# Adafruit_SHT40.net
KiCad netlist of a schematic drawn in EAGLE
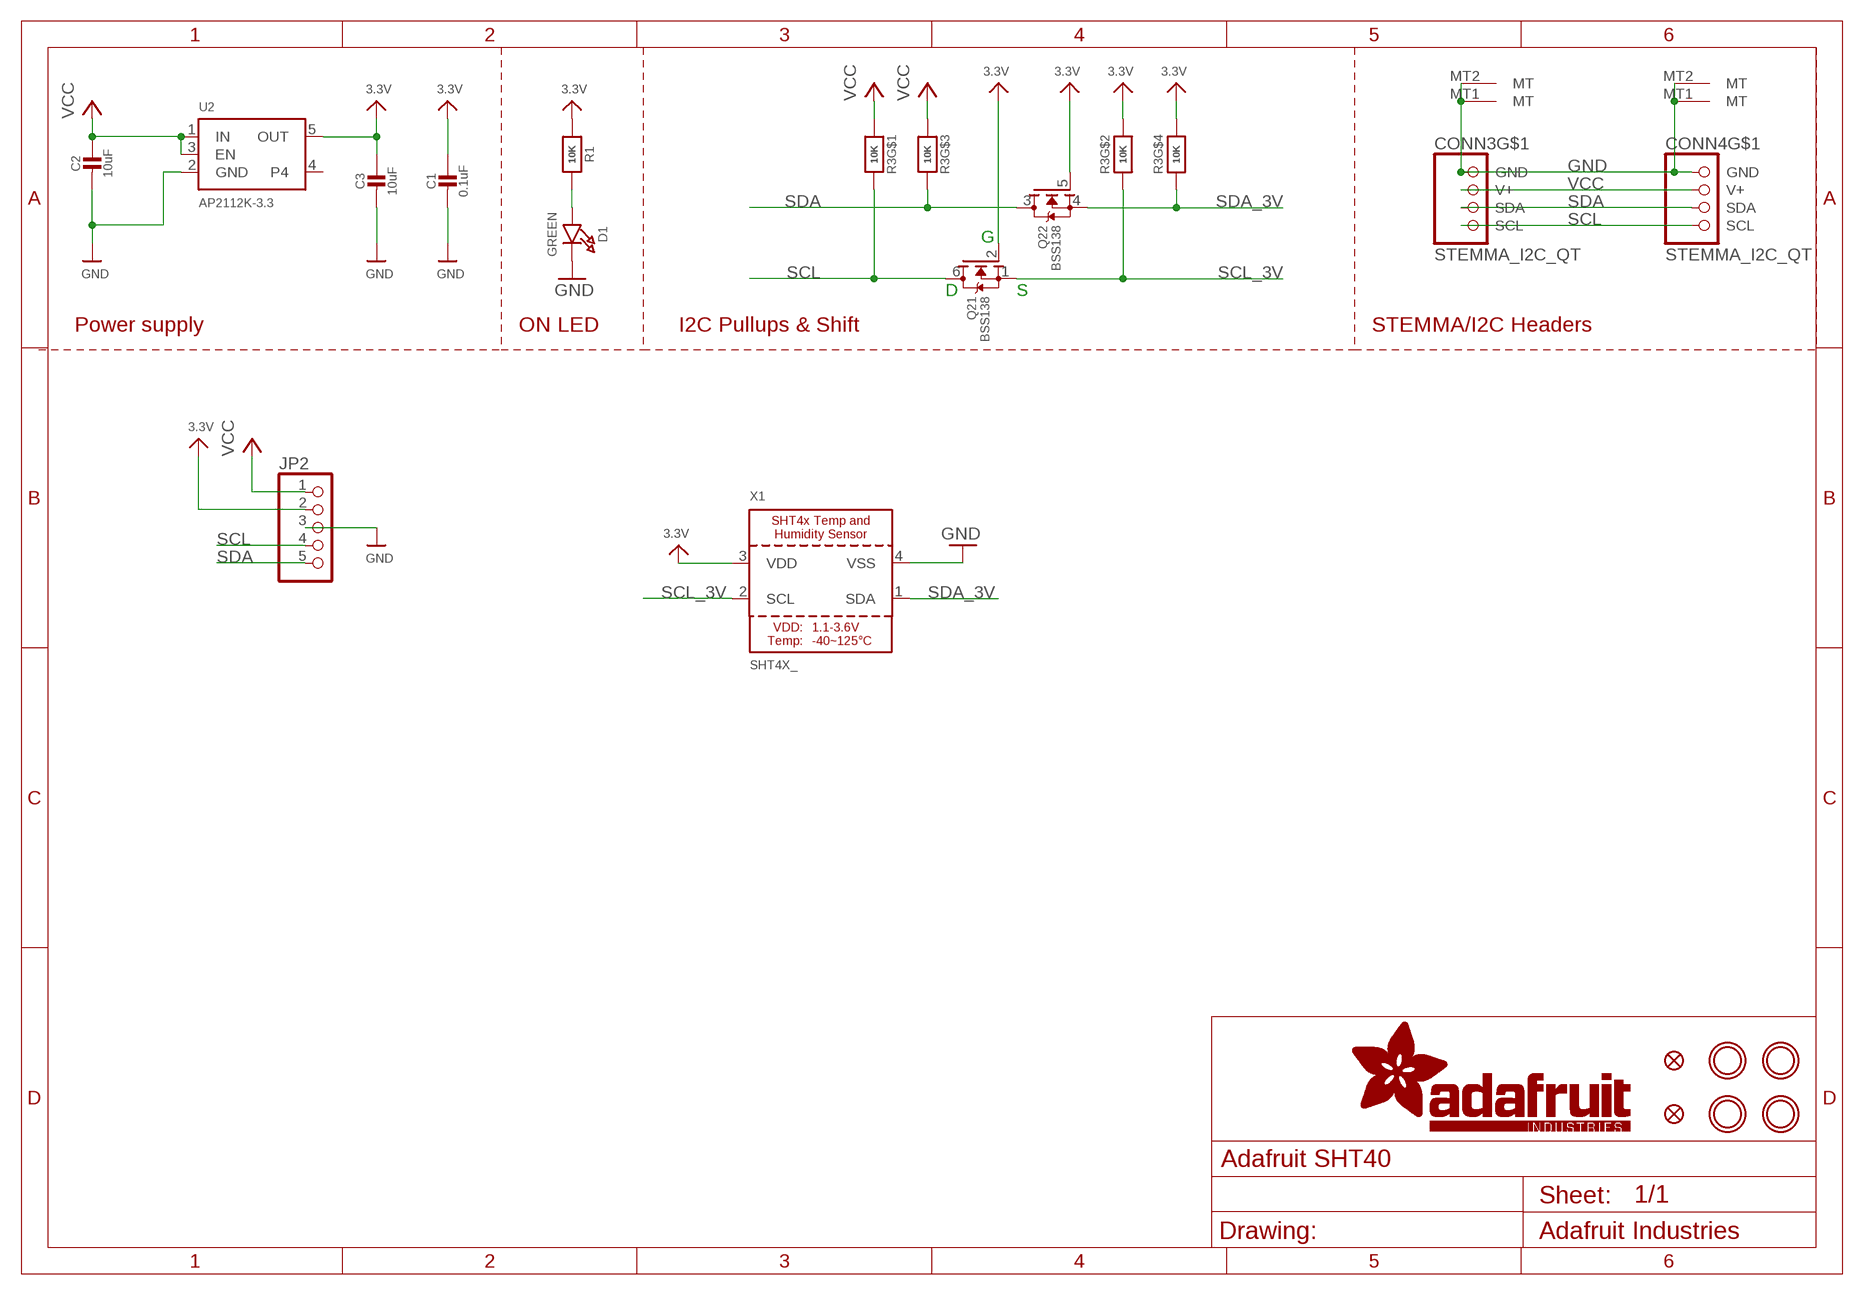
[diagram p0: schematic, sheet 1]

(export (version "E")
  (design (tool "Eeschema 10.0.6"))
  (components
    (comp (ref "C1")
      (value "0.1uF")
      (footprint "eagle-import:0603-NO")
      (libsource (lib "eagle-import") (part "CAP_CERAMIC0603_NO"))
    )
    (comp (ref "C2")
      (value "10uF")
      (footprint "eagle-import:0805-NO")
      (libsource (lib "eagle-import") (part "CAP_CERAMIC0805-NOOUTLINE"))
    )
    (comp (ref "C3")
      (value "10uF")
      (footprint "eagle-import:0805-NO")
      (libsource (lib "eagle-import") (part "CAP_CERAMIC0805-NOOUTLINE"))
    )
    (comp (ref "CONN3")
      (value "STEMMA_I2C_QT")
      (footprint "eagle-import:JST_SH4")
      (libsource (lib "eagle-import") (part "STEMMA_I2C_QT"))
    )
    (comp (ref "CONN4")
      (value "STEMMA_I2C_QT")
      (footprint "eagle-import:JST_SH4")
      (libsource (lib "eagle-import") (part "STEMMA_I2C_QT"))
    )
    (comp (ref "D1")
      (value "GREEN")
      (footprint "eagle-import:CHIPLED_0603_NOOUTLINE")
      (libsource (lib "eagle-import") (part "LED0603_NOOUTLINE"))
    )
    (comp (ref "FID3")
      (value "FIDUCIAL_1MM")
      (footprint "eagle-import:FIDUCIAL_1MM")
      (libsource (lib "eagle-import") (part "FIDUCIAL_1MM"))
    )
    (comp (ref "FID4")
      (value "FIDUCIAL_1MM")
      (footprint "eagle-import:FIDUCIAL_1MM")
      (libsource (lib "eagle-import") (part "FIDUCIAL_1MM"))
    )
    (comp (ref "JP2")
      (value "HEADER-1X570MIL")
      (footprint "eagle-import:1X05_ROUND_70")
      (libsource (lib "eagle-import") (part "HEADER-1X570MIL"))
    )
    (comp (ref "Q2")
      (value "BSS138")
      (footprint "eagle-import:SOT363")
      (libsource (lib "eagle-import") (part "MOSFET-N_DUAL"))
    )
    (comp (ref "R1")
      (value "10K")
      (footprint "eagle-import:0603-NO")
      (libsource (lib "eagle-import") (part "RESISTOR_0603_NOOUT"))
    )
    (comp (ref "R3")
      (value "10K")
      (footprint "eagle-import:RESPACK_4X0603")
      (libsource (lib "eagle-import") (part "RESISTOR_4PACK"))
    )
    (comp (ref "U$1")
      (value "MOUNTINGHOLE2.5")
      (footprint "eagle-import:MOUNTINGHOLE_2.5_PLATED")
      (libsource (lib "eagle-import") (part "MOUNTINGHOLE2.5"))
    )
    (comp (ref "U$17")
      (value "MOUNTINGHOLE2.5")
      (footprint "eagle-import:MOUNTINGHOLE_2.5_PLATED")
      (libsource (lib "eagle-import") (part "MOUNTINGHOLE2.5"))
    )
    (comp (ref "U$19")
      (value "MOUNTINGHOLE2.5")
      (footprint "eagle-import:MOUNTINGHOLE_2.5_PLATED")
      (libsource (lib "eagle-import") (part "MOUNTINGHOLE2.5"))
    )
    (comp (ref "U$21")
      (value "MOUNTINGHOLE2.5")
      (footprint "eagle-import:MOUNTINGHOLE_2.5_PLATED")
      (libsource (lib "eagle-import") (part "MOUNTINGHOLE2.5"))
    )
    (comp (ref "U2")
      (value "AP2112K-3.3")
      (footprint "eagle-import:SOT23-5")
      (libsource (lib "eagle-import") (part "VREG_SOT23-5"))
    )
    (comp (ref "X1")
      (value "SHT4X_")
      (footprint "eagle-import:SHT4X")
      (libsource (lib "eagle-import") (part "SHT4X_"))
    )
  )
  (nets
    (net (code "1") (name "/SCL") (class "Default")
      (node (ref "CONN3") (pin "4") (pinfunction "SCL_4") (pintype "passive"))
      (node (ref "CONN4") (pin "4") (pinfunction "SCL_4") (pintype "passive"))
      (node (ref "JP2") (pin "4") (pinfunction "4_4") (pintype "passive"))
      (node (ref "Q2") (pin "6") (pinfunction "D_6") (pintype "bidirectional"))
      (node (ref "R3") (pin "8") (pinfunction "2_8") (pintype "passive"))
    )
    (net (code "2") (name "/SCL_3V") (class "Default")
      (node (ref "Q2") (pin "1") (pinfunction "S_1") (pintype "bidirectional"))
      (node (ref "R3") (pin "7") (pinfunction "2_7") (pintype "passive"))
      (node (ref "X1") (pin "2") (pinfunction "SCL_2") (pintype "bidirectional"))
    )
    (net (code "3") (name "/SDA") (class "Default")
      (node (ref "CONN3") (pin "3") (pinfunction "SDA_3") (pintype "passive"))
      (node (ref "CONN4") (pin "3") (pinfunction "SDA_3") (pintype "passive"))
      (node (ref "JP2") (pin "5") (pinfunction "5_5") (pintype "passive"))
      (node (ref "Q2") (pin "3") (pinfunction "D_3") (pintype "bidirectional"))
      (node (ref "R3") (pin "6") (pinfunction "2_6") (pintype "passive"))
    )
    (net (code "4") (name "/SDA_3V") (class "Default")
      (node (ref "Q2") (pin "4") (pinfunction "S_4") (pintype "bidirectional"))
      (node (ref "R3") (pin "5") (pinfunction "2_5") (pintype "passive"))
      (node (ref "X1") (pin "1") (pinfunction "SDA_1") (pintype "bidirectional"))
    )
    (net (code "5") (name "3.3V") (class "Default")
      (node (ref "C1") (pin "1") (pinfunction "1_1") (pintype "passive"))
      (node (ref "C3") (pin "1") (pinfunction "1_1") (pintype "passive"))
      (node (ref "JP2") (pin "2") (pinfunction "2_2") (pintype "passive"))
      (node (ref "Q2") (pin "2") (pinfunction "G_2") (pintype "bidirectional"))
      (node (ref "Q2") (pin "5") (pinfunction "G_5") (pintype "bidirectional"))
      (node (ref "R1") (pin "1") (pinfunction "1_1") (pintype "passive"))
      (node (ref "R3") (pin "2") (pinfunction "1_2") (pintype "passive"))
      (node (ref "R3") (pin "4") (pinfunction "1_4") (pintype "passive"))
      (node (ref "U2") (pin "5") (pinfunction "OUT_5") (pintype "power_in"))
      (node (ref "X1") (pin "3") (pinfunction "VDD_3") (pintype "power_in"))
    )
    (net (code "6") (name "GND") (class "Default")
      (node (ref "C1") (pin "2") (pinfunction "2_2") (pintype "passive"))
      (node (ref "C2") (pin "2") (pinfunction "2_2") (pintype "passive"))
      (node (ref "C3") (pin "2") (pinfunction "2_2") (pintype "passive"))
      (node (ref "CONN3") (pin "1") (pinfunction "GND_1") (pintype "passive"))
      (node (ref "CONN3") (pin "MT1") (pinfunction "MT_MT1") (pintype "bidirectional"))
      (node (ref "CONN3") (pin "MT2") (pinfunction "MT_MT2") (pintype "bidirectional"))
      (node (ref "CONN4") (pin "1") (pinfunction "GND_1") (pintype "passive"))
      (node (ref "CONN4") (pin "MT1") (pinfunction "MT_MT1") (pintype "bidirectional"))
      (node (ref "CONN4") (pin "MT2") (pinfunction "MT_MT2") (pintype "bidirectional"))
      (node (ref "D1") (pin "C") (pinfunction "C_C") (pintype "passive"))
      (node (ref "JP2") (pin "3") (pinfunction "3_3") (pintype "passive"))
      (node (ref "U2") (pin "2") (pinfunction "GND_2") (pintype "power_in"))
      (node (ref "X1") (pin "4") (pinfunction "VSS_4") (pintype "power_in"))
    )
    (net (code "7") (name "Net-(D1-PadA)") (class "Default")
      (node (ref "D1") (pin "A") (pinfunction "A_A") (pintype "passive"))
      (node (ref "R1") (pin "2") (pinfunction "2_2") (pintype "passive"))
    )
    (net (code "8") (name "VCC") (class "Default")
      (node (ref "C2") (pin "1") (pinfunction "1_1") (pintype "passive"))
      (node (ref "CONN3") (pin "2") (pinfunction "V+_2") (pintype "passive"))
      (node (ref "CONN4") (pin "2") (pinfunction "V+_2") (pintype "passive"))
      (node (ref "JP2") (pin "1") (pinfunction "1_1") (pintype "passive"))
      (node (ref "R3") (pin "1") (pinfunction "1_1") (pintype "passive"))
      (node (ref "R3") (pin "3") (pinfunction "1_3") (pintype "passive"))
      (node (ref "U2") (pin "1") (pinfunction "IN_1") (pintype "power_in"))
      (node (ref "U2") (pin "3") (pinfunction "EN_3") (pintype "input"))
    )
    (net (code "9") (name "unconnected-(U2-P4-Pad4)") (class "Default")
      (node (ref "U2") (pin "4") (pinfunction "P4_4") (pintype "bidirectional"))
    )
  )
)
